# v1_0.net
KiCad netlist of a schematic drawn in Altium Designer
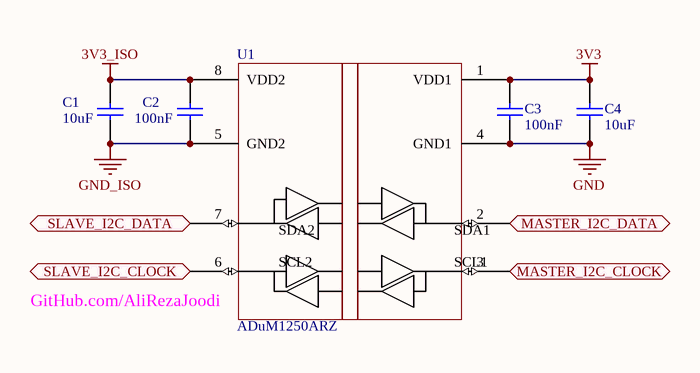
[diagram p0: v1.0.SchDoc]

(export (version "E")
  (design (tool "Eeschema 10.0.6"))
  (components
    (comp (ref "C1")
      (value "10uF")
      (footprint "Capacitor_Ceramic:SMD_0805")
      (description "Capacitor, Ceramic Multilayer")
      (libsource (lib "General") (part "Capacitor_Ceramic"))
    )
    (comp (ref "C2")
      (value "100nF")
      (footprint "Capacitor_Ceramic:SMD_0805")
      (description "Capacitor, Ceramic Multilayer")
      (libsource (lib "General") (part "Capacitor_Ceramic"))
    )
    (comp (ref "C3")
      (value "100nF")
      (footprint "Capacitor_Ceramic:SMD_0805")
      (description "Capacitor, Ceramic Multilayer")
      (libsource (lib "General") (part "Capacitor_Ceramic"))
    )
    (comp (ref "C4")
      (value "10uF")
      (footprint "Capacitor_Ceramic:SMD_0805")
      (description "Capacitor, Ceramic Multilayer")
      (libsource (lib "General") (part "Capacitor_Ceramic"))
    )
    (comp (ref "U1")
      (value "ADuM1250ARZ")
      (description "IC, Isolated I2C")
      (fields (field (name "1_PART NUMBER") "ADUM1250ARZ"))
      (libsource (lib "IC") (part "Isolator_ADuM1250"))
    )
  )
  (nets
    (net (code "1") (name "/MASTER_I2C_CLOCK") (class "Default")
      (node (ref "U1") (pin "3") (pinfunction "SCL1_3") (pintype "bidirectional"))
    )
    (net (code "2") (name "/MASTER_I2C_DATA") (class "Default")
      (node (ref "U1") (pin "2") (pinfunction "SDA1_2") (pintype "bidirectional"))
    )
    (net (code "3") (name "/SLAVE_I2C_CLOCK") (class "Default")
      (node (ref "U1") (pin "6") (pinfunction "SCL2_6") (pintype "bidirectional"))
    )
    (net (code "4") (name "/SLAVE_I2C_DATA") (class "Default")
      (node (ref "U1") (pin "7") (pinfunction "SDA2_7") (pintype "bidirectional"))
    )
    (net (code "5") (name "3V3") (class "Default")
      (node (ref "C3") (pin "2") (pinfunction "2_2") (pintype "passive"))
      (node (ref "C4") (pin "1") (pinfunction "1_1") (pintype "passive"))
      (node (ref "U1") (pin "1") (pinfunction "VDD1_1") (pintype "passive"))
    )
    (net (code "6") (name "3V3_ISO") (class "Default")
      (node (ref "C1") (pin "1") (pinfunction "1_1") (pintype "passive"))
      (node (ref "C2") (pin "2") (pinfunction "2_2") (pintype "passive"))
      (node (ref "U1") (pin "8") (pinfunction "VDD2_8") (pintype "passive"))
    )
    (net (code "7") (name "GND") (class "Default")
      (node (ref "C3") (pin "1") (pinfunction "1_1") (pintype "passive"))
      (node (ref "C4") (pin "2") (pinfunction "2_2") (pintype "passive"))
      (node (ref "U1") (pin "4") (pinfunction "GND1_4") (pintype "passive"))
    )
    (net (code "8") (name "GND_ISO") (class "Default")
      (node (ref "C1") (pin "2") (pinfunction "2_2") (pintype "passive"))
      (node (ref "C2") (pin "1") (pinfunction "1_1") (pintype "passive"))
      (node (ref "U1") (pin "5") (pinfunction "GND2_5") (pintype "passive"))
    )
  )
)
